# co2.net
KiCad netlist of a schematic drawn in EAGLE
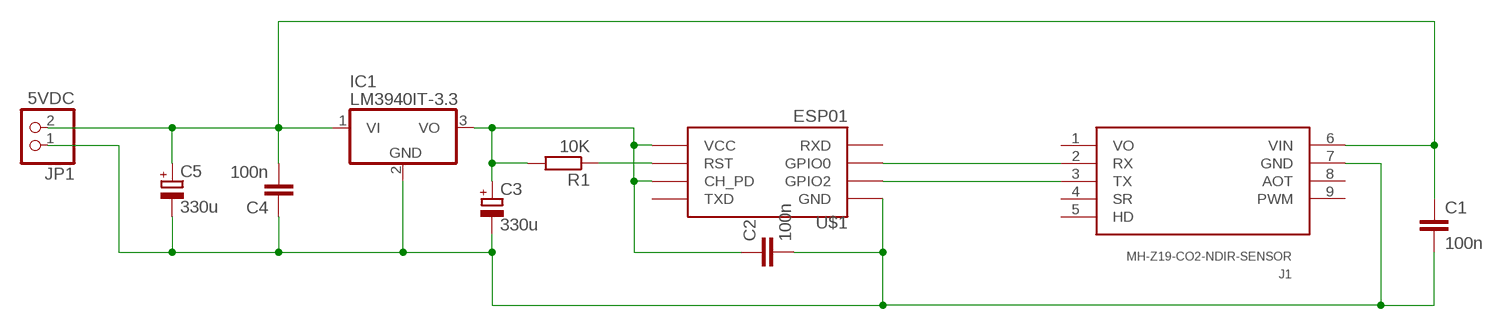
[diagram p0: schematic, sheet 1]

(export (version "E")
  (design (tool "Eeschema 10.0.6"))
  (components
    (comp (ref "C1")
      (value "100n")
      (footprint "eagle-import:C050-025X075")
      (libsource (lib "eagle-import") (part "C-EU050-025X075"))
    )
    (comp (ref "C2")
      (value "100n")
      (footprint "eagle-import:C050-025X075")
      (libsource (lib "eagle-import") (part "C-EU050-025X075"))
    )
    (comp (ref "C3")
      (value "330u")
      (footprint "eagle-import:E2,5-6")
      (libsource (lib "eagle-import") (part "CPOL-EUE2.5-6"))
    )
    (comp (ref "C4")
      (value "100n")
      (footprint "eagle-import:C050-025X075")
      (libsource (lib "eagle-import") (part "C-EU050-025X075"))
    )
    (comp (ref "C5")
      (value "330u")
      (footprint "eagle-import:E2,5-6")
      (libsource (lib "eagle-import") (part "CPOL-EUE2.5-6"))
    )
    (comp (ref "IC1")
      (value "LM3940IT-3.3")
      (footprint "eagle-import:TO220H")
      (libsource (lib "eagle-import") (part "78T05"))
    )
    (comp (ref "J1")
      (value "MH-Z19-CO2-NDIR-SENSOR")
      (footprint "eagle-import:MH-Z19")
      (libsource (lib "eagle-import") (part "MH-Z19-CO2-NDIR-SENSOR"))
    )
    (comp (ref "JP1")
      (value "5VDC")
      (footprint "eagle-import:1X02")
      (libsource (lib "eagle-import") (part "PINHD-1X2"))
    )
    (comp (ref "R1")
      (value "10K")
      (footprint "eagle-import:0204_7")
      (libsource (lib "eagle-import") (part "R-EU_0204/7"))
    )
    (comp (ref "U$1")
      (value "ESP01")
      (footprint "eagle-import:ESP01")
      (libsource (lib "eagle-import") (part "ESP01"))
    )
  )
  (nets
    (net (code "1") (name "/VO") (class "Default")
      (node (ref "J1") (pin "1") (pinfunction "VO_1") (pintype "power_in"))
    )
    (net (code "2") (name "Net-(IC1-GND)") (class "Default")
      (node (ref "C1") (pin "2") (pinfunction "2_2") (pintype "passive"))
      (node (ref "C2") (pin "2") (pinfunction "2_2") (pintype "passive"))
      (node (ref "C3") (pin "-") (pinfunction "-_-") (pintype "passive"))
      (node (ref "C4") (pin "1") (pinfunction "1_1") (pintype "passive"))
      (node (ref "C5") (pin "-") (pinfunction "-_-") (pintype "passive"))
      (node (ref "IC1") (pin "2") (pinfunction "GND_2") (pintype "passive"))
      (node (ref "J1") (pin "7") (pinfunction "GND_7") (pintype "power_in"))
      (node (ref "JP1") (pin "1") (pinfunction "1_1") (pintype "passive"))
      (node (ref "U$1") (pin "GND") (pinfunction "GND_GND") (pintype "bidirectional"))
    )
    (net (code "3") (name "Net-(IC1-VI)") (class "Default")
      (node (ref "C1") (pin "1") (pinfunction "1_1") (pintype "passive"))
      (node (ref "C4") (pin "2") (pinfunction "2_2") (pintype "passive"))
      (node (ref "C5") (pin "+") (pinfunction "+_+") (pintype "passive"))
      (node (ref "IC1") (pin "1") (pinfunction "VI_1") (pintype "input"))
      (node (ref "J1") (pin "6") (pinfunction "VIN_6") (pintype "power_in"))
      (node (ref "JP1") (pin "2") (pinfunction "2_2") (pintype "passive"))
    )
    (net (code "4") (name "Net-(IC1-VO)") (class "Default")
      (node (ref "C2") (pin "1") (pinfunction "1_1") (pintype "passive"))
      (node (ref "C3") (pin "+") (pinfunction "+_+") (pintype "passive"))
      (node (ref "IC1") (pin "3") (pinfunction "VO_3") (pintype "passive"))
      (node (ref "R1") (pin "2") (pinfunction "2_2") (pintype "passive"))
      (node (ref "U$1") (pin "CH_PD") (pinfunction "CH_PD_CH_PD") (pintype "bidirectional"))
      (node (ref "U$1") (pin "VCC") (pinfunction "VCC_VCC") (pintype "bidirectional"))
    )
    (net (code "5") (name "Net-(J1-RX)") (class "Default")
      (node (ref "J1") (pin "2") (pinfunction "RX_2") (pintype "input"))
      (node (ref "U$1") (pin "GPIO0") (pinfunction "GPIO0_GPIO0") (pintype "bidirectional"))
    )
    (net (code "6") (name "Net-(J1-TX)") (class "Default")
      (node (ref "J1") (pin "3") (pinfunction "TX_3") (pintype "output"))
      (node (ref "U$1") (pin "GPIO2") (pinfunction "GPIO2_GPIO2") (pintype "bidirectional"))
    )
    (net (code "7") (name "Net-(R1-Pad1)") (class "Default")
      (node (ref "R1") (pin "1") (pinfunction "1_1") (pintype "passive"))
      (node (ref "U$1") (pin "RST") (pinfunction "RST_RST") (pintype "bidirectional"))
    )
    (net (code "8") (name "unconnected-(J1-AOT-Pad8)") (class "Default")
      (node (ref "J1") (pin "8") (pinfunction "AOT_8") (pintype "no_connect"))
    )
    (net (code "9") (name "unconnected-(J1-HD-Pad5)") (class "Default")
      (node (ref "J1") (pin "5") (pinfunction "HD_5") (pintype "input"))
    )
    (net (code "10") (name "unconnected-(J1-PWM-Pad9)") (class "Default")
      (node (ref "J1") (pin "9") (pinfunction "PWM_9") (pintype "output"))
    )
    (net (code "11") (name "unconnected-(J1-SR-Pad4)") (class "Default")
      (node (ref "J1") (pin "4") (pinfunction "SR_4") (pintype "no_connect"))
    )
    (net (code "12") (name "unconnected-(U$1-RXD-PadRX)") (class "Default")
      (node (ref "U$1") (pin "RX") (pinfunction "RXD_RX") (pintype "bidirectional"))
    )
    (net (code "13") (name "unconnected-(U$1-TXD-PadTX)") (class "Default")
      (node (ref "U$1") (pin "TX") (pinfunction "TXD_TX") (pintype "bidirectional"))
    )
  )
)
